# MaxMotor.net
KiCad netlist of a schematic drawn in EAGLE
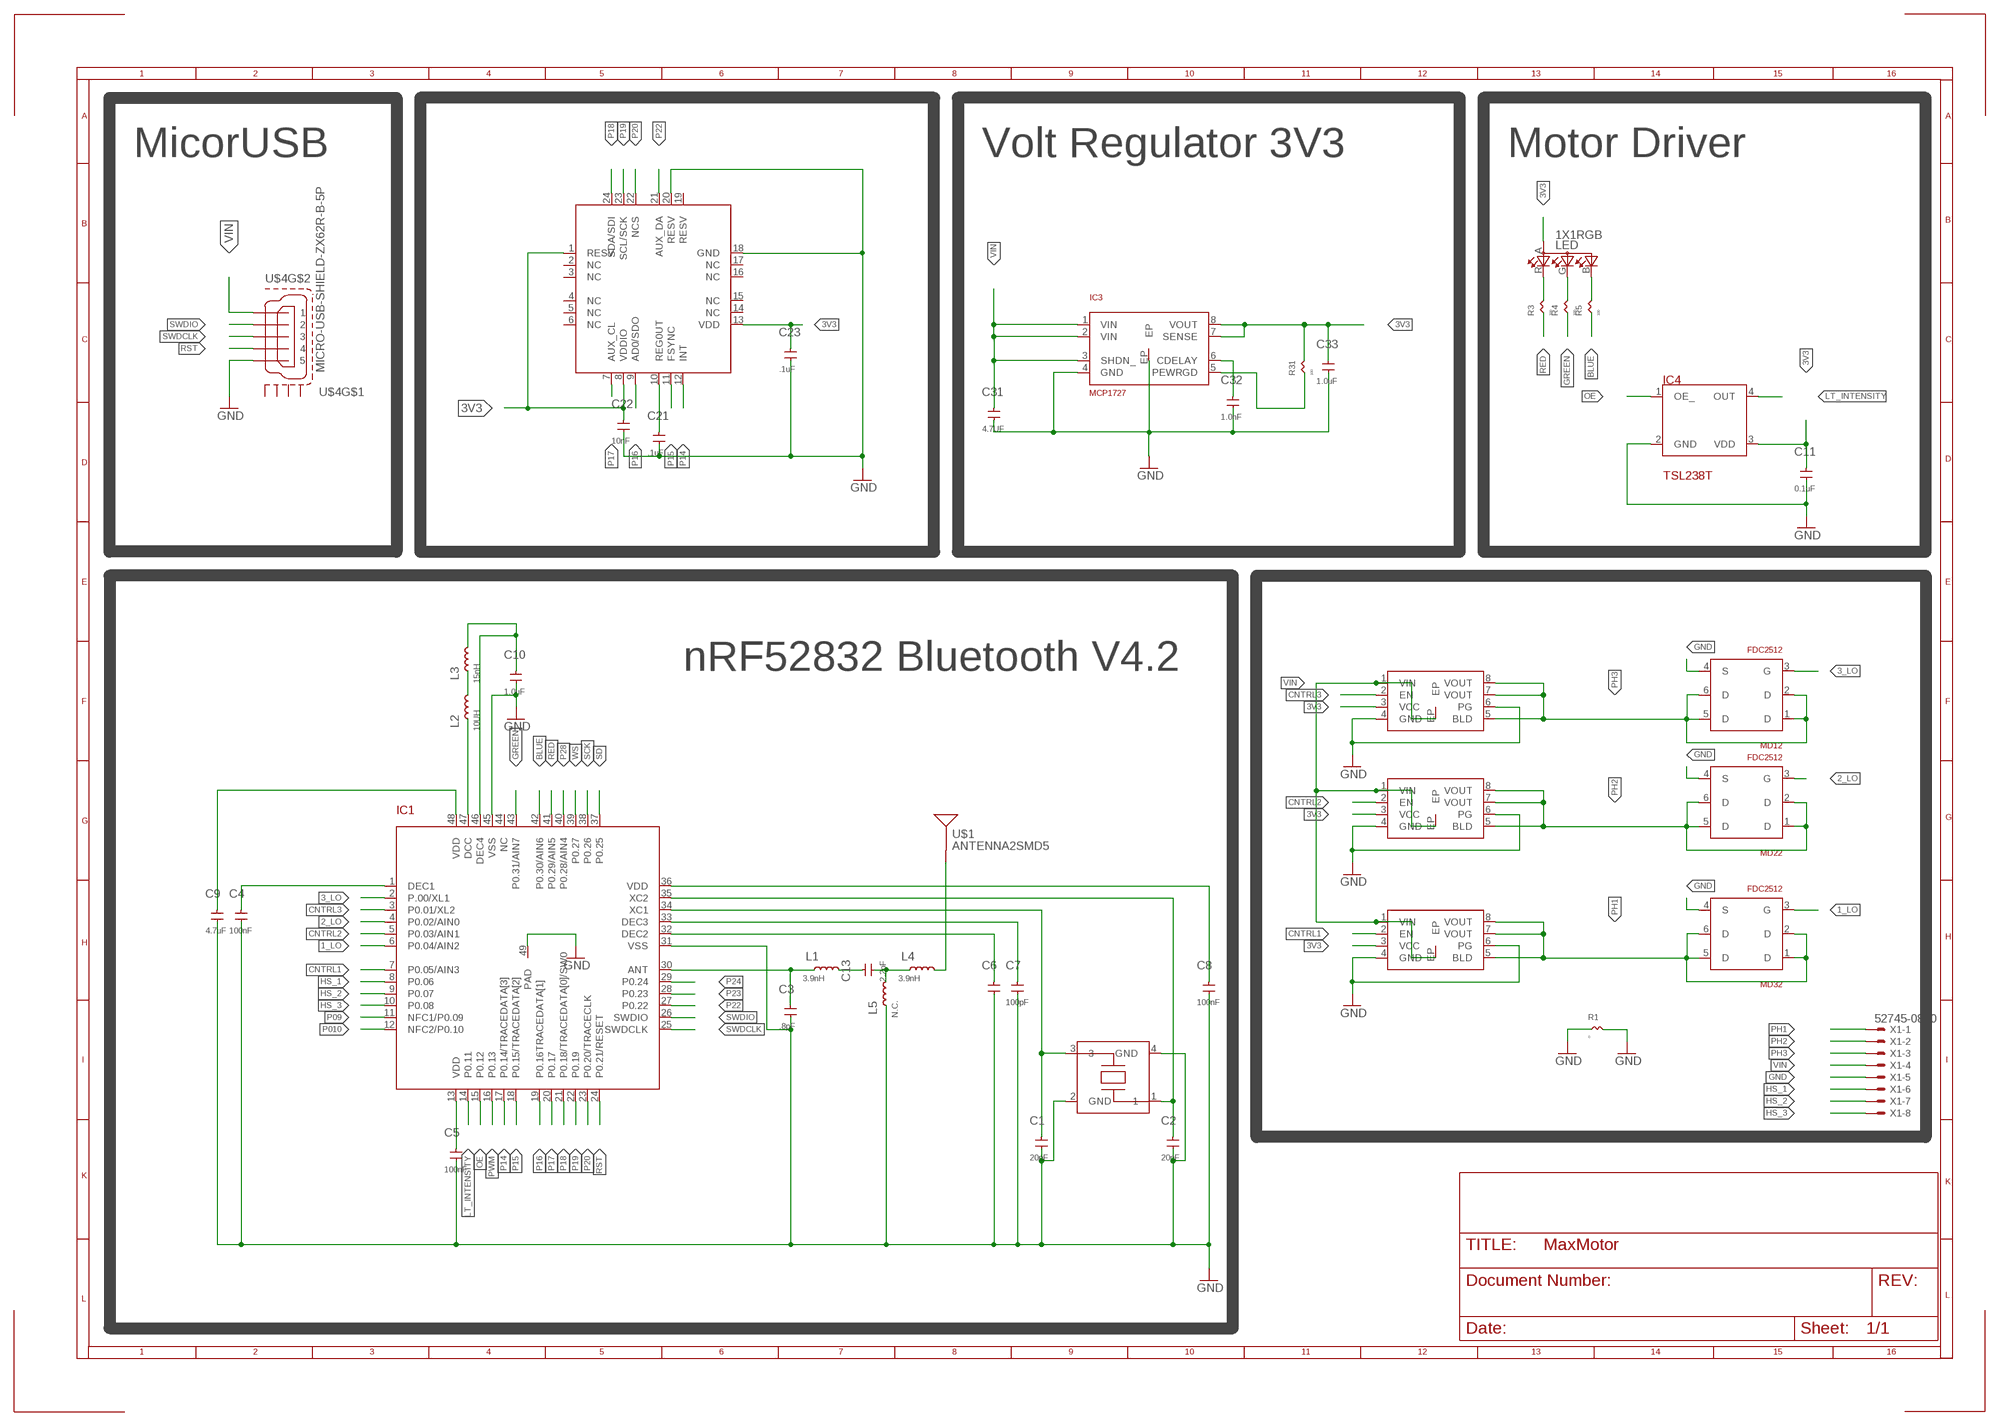
[diagram p0: schematic, sheet 1, part 1 of 2]
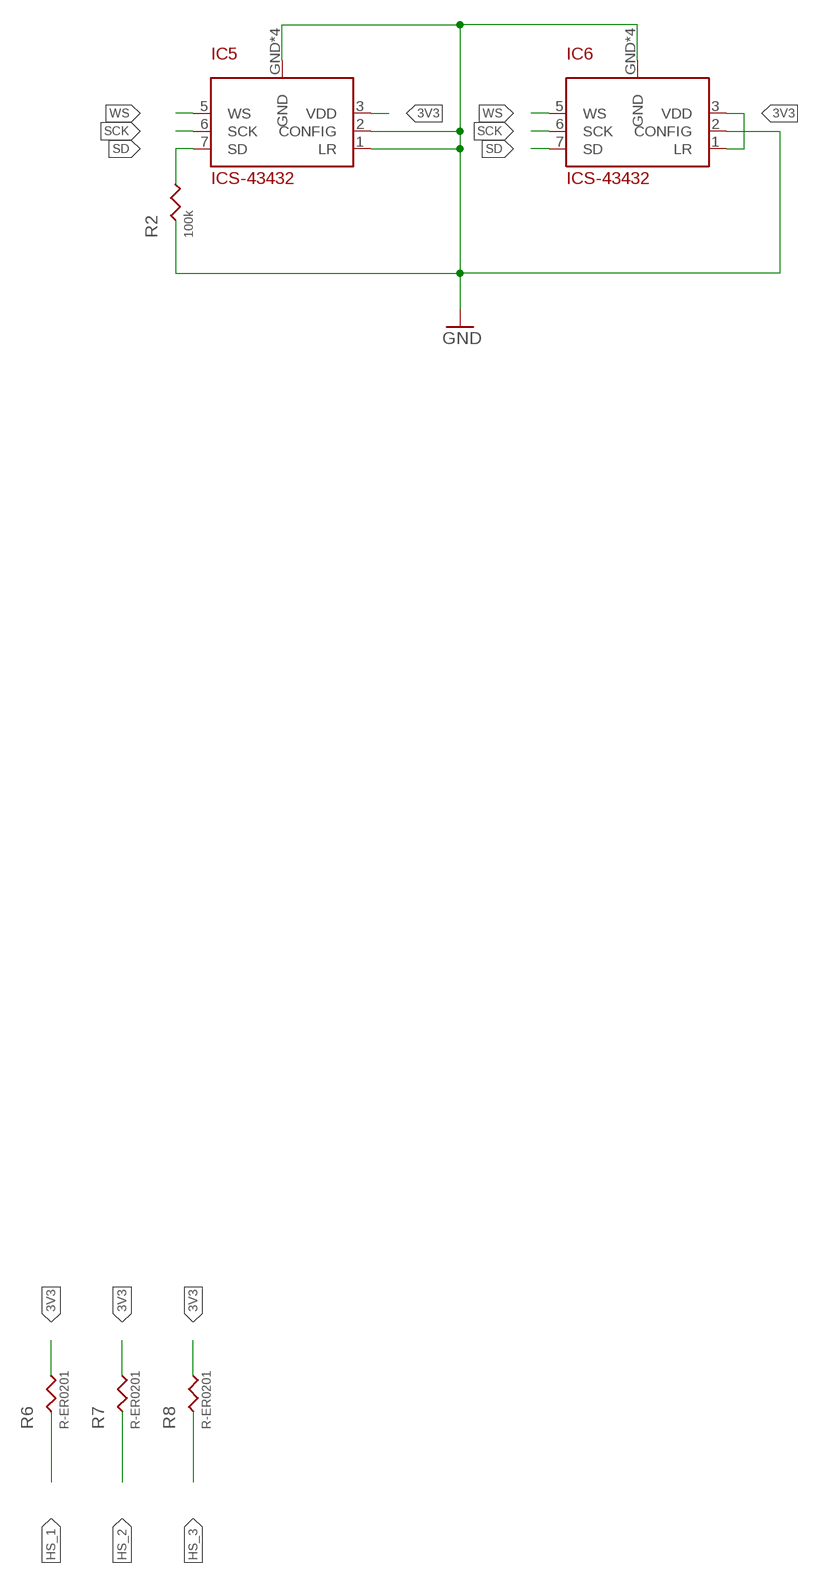
[diagram p1: schematic, sheet 1, part 2 of 2]

(export (version "E")
  (design (tool "Eeschema 10.0.6"))
  (components
    (comp (ref "C1")
      (value "20pF")
      (footprint "eagle-import:C0402")
      (libsource (lib "eagle-import") (part "C-ERC0402"))
    )
    (comp (ref "C2")
      (value "20pF")
      (footprint "eagle-import:C0402")
      (libsource (lib "eagle-import") (part "C-ERC0402"))
    )
    (comp (ref "C3")
      (value ".8pF")
      (footprint "eagle-import:C0402")
      (libsource (lib "eagle-import") (part "C-ERC0402"))
    )
    (comp (ref "C4")
      (value "100nF")
      (footprint "eagle-import:C0402")
      (libsource (lib "eagle-import") (part "C-ERC0402"))
    )
    (comp (ref "C5")
      (value "100nF")
      (footprint "eagle-import:C0402")
      (libsource (lib "eagle-import") (part "C-ERC0402"))
    )
    (comp (ref "C6")
      (value "C-ERC0402")
      (footprint "eagle-import:C0402")
      (libsource (lib "eagle-import") (part "C-ERC0402"))
    )
    (comp (ref "C7")
      (value "100pF")
      (footprint "eagle-import:C0402")
      (libsource (lib "eagle-import") (part "C-ERC0402"))
    )
    (comp (ref "C8")
      (value "100nF")
      (footprint "eagle-import:C0402")
      (libsource (lib "eagle-import") (part "C-ERC0402"))
    )
    (comp (ref "C9")
      (value "4.7uF")
      (footprint "eagle-import:C0805")
      (libsource (lib "eagle-import") (part "C-ER"))
    )
    (comp (ref "C10")
      (value "1.0uF")
      (footprint "eagle-import:C0402")
      (libsource (lib "eagle-import") (part "C-ERC0402"))
    )
    (comp (ref "C11")
      (value "0.1uF")
      (footprint "eagle-import:C0402")
      (libsource (lib "eagle-import") (part "C-ERC0402"))
    )
    (comp (ref "C13")
      (value "2.2pF")
      (footprint "eagle-import:C0402")
      (libsource (lib "eagle-import") (part "C-ERC0402"))
    )
    (comp (ref "C21")
      (value ".1uF")
      (footprint "eagle-import:C0402")
      (libsource (lib "eagle-import") (part "C-ERC0402"))
    )
    (comp (ref "C22")
      (value "10nF")
      (footprint "eagle-import:C0402")
      (libsource (lib "eagle-import") (part "C-ERC0402"))
    )
    (comp (ref "C23")
      (value ".1uF")
      (footprint "eagle-import:C0402")
      (libsource (lib "eagle-import") (part "C-ERC0402"))
    )
    (comp (ref "C31")
      (value "4.7UF")
      (footprint "eagle-import:C0805")
      (libsource (lib "eagle-import") (part "C-ER"))
    )
    (comp (ref "C32")
      (value "1.0nF")
      (footprint "eagle-import:C0402")
      (libsource (lib "eagle-import") (part "C-ERC0402"))
    )
    (comp (ref "C33")
      (value "1.0uF")
      (footprint "eagle-import:C0402")
      (libsource (lib "eagle-import") (part "C-ERC0402"))
    )
    (comp (ref "IC1")
      (value "NRF52832")
      (footprint "eagle-import:QFN48")
      (libsource (lib "eagle-import") (part "NRF52832"))
    )
    (comp (ref "IC2")
      (value "MPU9250_CORRECTED")
      (footprint "eagle-import:3X3_24_QFN_CORRECTED")
      (libsource (lib "eagle-import") (part "MPU9250_CORRECTED"))
    )
    (comp (ref "IC3")
      (value "MCP1727")
      (footprint "eagle-import:DFN8-3X3")
      (libsource (lib "eagle-import") (part "MCP1727"))
    )
    (comp (ref "IC4")
      (value "TSL238T")
      (footprint "eagle-import:T4")
      (libsource (lib "eagle-import") (part "TSL238T"))
    )
    (comp (ref "IC5")
      (value "ICS-43432")
      (footprint "eagle-import:ICS-43432")
      (libsource (lib "eagle-import") (part "ICS-43432"))
    )
    (comp (ref "IC6")
      (value "ICS-43432")
      (footprint "eagle-import:ICS-43432")
      (libsource (lib "eagle-import") (part "ICS-43432"))
    )
    (comp (ref "L1")
      (value "3.9nH")
      (footprint "eagle-import:R0402")
      (libsource (lib "eagle-import") (part "L-ERL402"))
    )
    (comp (ref "L2")
      (value "10UH")
      (footprint "eagle-import:R0603")
      (libsource (lib "eagle-import") (part "L-ERL603"))
    )
    (comp (ref "L3")
      (value "15nH")
      (footprint "eagle-import:R0402")
      (libsource (lib "eagle-import") (part "L-ERL402"))
    )
    (comp (ref "L4")
      (value "3.9nH")
      (footprint "eagle-import:R0402")
      (libsource (lib "eagle-import") (part "L-ERL402"))
    )
    (comp (ref "L5")
      (value "N.C.")
      (footprint "eagle-import:R0402")
      (libsource (lib "eagle-import") (part "L-ERL402"))
    )
    (comp (ref "LED")
      (value "1X1RGB")
      (footprint "eagle-import:1X1")
      (libsource (lib "eagle-import") (part "1X1RGB"))
    )
    (comp (ref "MD12")
      (value "FDC2512")
      (footprint "eagle-import:SSOT6")
      (libsource (lib "eagle-import") (part "FDC2512"))
    )
    (comp (ref "MD22")
      (value "FDC2512")
      (footprint "eagle-import:SSOT6")
      (libsource (lib "eagle-import") (part "FDC2512"))
    )
    (comp (ref "MD32")
      (value "FDC2512")
      (footprint "eagle-import:SSOT6")
      (libsource (lib "eagle-import") (part "FDC2512"))
    )
    (comp (ref "R1")
      (value "0")
      (footprint "eagle-import:R0402")
      (libsource (lib "eagle-import") (part "R-ER-TINYR402"))
    )
    (comp (ref "R2")
      (value "100k")
      (footprint "eagle-import:R0402")
      (libsource (lib "eagle-import") (part "R-ERR0402"))
    )
    (comp (ref "R3")
      (value "100")
      (footprint "eagle-import:R0402")
      (libsource (lib "eagle-import") (part "R-ER-TINYR402"))
    )
    (comp (ref "R4")
      (value "100")
      (footprint "eagle-import:R0402")
      (libsource (lib "eagle-import") (part "R-ER-TINYR402"))
    )
    (comp (ref "R5")
      (value "100")
      (footprint "eagle-import:R0402")
      (libsource (lib "eagle-import") (part "R-ER-TINYR402"))
    )
    (comp (ref "R6")
      (value "R-ER0201")
      (footprint "eagle-import:R0201")
      (libsource (lib "eagle-import") (part "R-ER0201"))
    )
    (comp (ref "R7")
      (value "R-ER0201")
      (footprint "eagle-import:R0201")
      (libsource (lib "eagle-import") (part "R-ER0201"))
    )
    (comp (ref "R8")
      (value "R-ER0201")
      (footprint "eagle-import:R0201")
      (libsource (lib "eagle-import") (part "R-ER0201"))
    )
    (comp (ref "R31")
      (value "100")
      (footprint "eagle-import:R0402")
      (libsource (lib "eagle-import") (part "R-ER-TINYR402"))
    )
    (comp (ref "U$1")
      (value "ANTENNA2SMD5")
      (footprint "eagle-import:ANTENNA-CHIP5")
      (libsource (lib "eagle-import") (part "ANTENNA2SMD5"))
    )
    (comp (ref "U$2")
      (value "NCP45524/25")
      (footprint "eagle-import:DFN8")
      (libsource (lib "eagle-import") (part "NCP45524/25"))
    )
    (comp (ref "U$4")
      (value "MICRO-USB-SHIELD-ZX62R-B-5P")
      (footprint "eagle-import:ZX62R-B-5P")
      (libsource (lib "eagle-import") (part "MICRO-USB-SHIELD-ZX62R-B-5P"))
    )
    (comp (ref "U$5")
      (value "NCP45524/25")
      (footprint "eagle-import:DFN8")
      (libsource (lib "eagle-import") (part "NCP45524/25"))
    )
    (comp (ref "U$6")
      (value "NCP45524/25")
      (footprint "eagle-import:DFN8")
      (libsource (lib "eagle-import") (part "NCP45524/25"))
    )
    (comp (ref "X1")
      (value "52745-0890")
      (footprint "eagle-import:52745-0890")
      (libsource (lib "eagle-import") (part "52745-0890"))
    )
    (comp (ref "XTL16M")
      (value "FA-128")
      (footprint "eagle-import:FA-128")
      (libsource (lib "eagle-import") (part "FA-128"))
    )
  )
  (nets
    (net (code "1") (name "1_LO") (class "Default")
      (node (ref "IC1") (pin "6") (pinfunction "P0.04/AIN2_6") (pintype "bidirectional"))
      (node (ref "MD32") (pin "3") (pinfunction "G_3") (pintype "bidirectional"))
    )
    (net (code "2") (name "2_LO") (class "Default")
      (node (ref "IC1") (pin "4") (pinfunction "P0.02/AIN0_4") (pintype "bidirectional"))
      (node (ref "MD22") (pin "3") (pinfunction "G_3") (pintype "bidirectional"))
    )
    (net (code "3") (name "3V3") (class "Default")
      (node (ref "C11") (pin "2") (pinfunction "P$2_2") (pintype "bidirectional"))
      (node (ref "C22") (pin "2") (pinfunction "P$2_2") (pintype "bidirectional"))
      (node (ref "C23") (pin "2") (pinfunction "P$2_2") (pintype "bidirectional"))
      (node (ref "C33") (pin "2") (pinfunction "P$2_2") (pintype "bidirectional"))
      (node (ref "C5") (pin "2") (pinfunction "P$2_2") (pintype "bidirectional"))
      (node (ref "C8") (pin "2") (pinfunction "P$2_2") (pintype "bidirectional"))
      (node (ref "C9") (pin "2") (pinfunction "P$2_2") (pintype "bidirectional"))
      (node (ref "IC1") (pin "13") (pinfunction "VDD_13") (pintype "bidirectional"))
      (node (ref "IC1") (pin "36") (pinfunction "VDD_36") (pintype "bidirectional"))
      (node (ref "IC1") (pin "48") (pinfunction "VDD_48") (pintype "bidirectional"))
      (node (ref "IC2") (pin "1") (pinfunction "RESV_1") (pintype "bidirectional"))
      (node (ref "IC2") (pin "13") (pinfunction "VDD_13") (pintype "bidirectional"))
      (node (ref "IC2") (pin "8") (pinfunction "VDDIO_8") (pintype "bidirectional"))
      (node (ref "IC3") (pin "7") (pinfunction "SENSE_7") (pintype "bidirectional"))
      (node (ref "IC3") (pin "8") (pinfunction "VOUT_8") (pintype "bidirectional"))
      (node (ref "IC4") (pin "3") (pinfunction "VDD_3") (pintype "bidirectional"))
      (node (ref "IC5") (pin "3") (pinfunction "VDD_3") (pintype "bidirectional"))
      (node (ref "IC6") (pin "1") (pinfunction "LR_1") (pintype "bidirectional"))
      (node (ref "IC6") (pin "3") (pinfunction "VDD_3") (pintype "bidirectional"))
      (node (ref "LED") (pin "A") (pinfunction "A2_A") (pintype "passive"))
      (node (ref "R31") (pin "2") (pinfunction "P$2_2") (pintype "bidirectional"))
      (node (ref "R6") (pin "2") (pinfunction "P$2_2") (pintype "bidirectional"))
      (node (ref "R7") (pin "2") (pinfunction "P$2_2") (pintype "bidirectional"))
      (node (ref "R8") (pin "2") (pinfunction "P$2_2") (pintype "bidirectional"))
      (node (ref "U$2") (pin "3") (pinfunction "VCC_3") (pintype "bidirectional"))
      (node (ref "U$5") (pin "3") (pinfunction "VCC_3") (pintype "bidirectional"))
      (node (ref "U$6") (pin "3") (pinfunction "VCC_3") (pintype "bidirectional"))
    )
    (net (code "4") (name "3_LO") (class "Default")
      (node (ref "IC1") (pin "2") (pinfunction "P.00/XL1_2") (pintype "bidirectional"))
      (node (ref "MD12") (pin "3") (pinfunction "G_3") (pintype "bidirectional"))
    )
    (net (code "5") (name "BLUE") (class "Default")
      (node (ref "IC1") (pin "42") (pinfunction "P0.30/AIN6_42") (pintype "bidirectional"))
      (node (ref "R5") (pin "1") (pinfunction "P$1_1") (pintype "bidirectional"))
    )
    (net (code "6") (name "CNTRL1") (class "Default")
      (node (ref "IC1") (pin "7") (pinfunction "P0.05/AIN3_7") (pintype "bidirectional"))
      (node (ref "U$6") (pin "2") (pinfunction "EN_2") (pintype "bidirectional"))
    )
    (net (code "7") (name "CNTRL2") (class "Default")
      (node (ref "IC1") (pin "5") (pinfunction "P0.03/AIN1_5") (pintype "bidirectional"))
      (node (ref "U$5") (pin "2") (pinfunction "EN_2") (pintype "bidirectional"))
    )
    (net (code "8") (name "CNTRL3") (class "Default")
      (node (ref "IC1") (pin "3") (pinfunction "P0.01/XL2_3") (pintype "bidirectional"))
      (node (ref "U$2") (pin "2") (pinfunction "EN_2") (pintype "bidirectional"))
    )
    (net (code "9") (name "GND") (class "Default")
      (node (ref "C1") (pin "1") (pinfunction "P$1_1") (pintype "bidirectional"))
      (node (ref "C10") (pin "1") (pinfunction "P$1_1") (pintype "bidirectional"))
      (node (ref "C11") (pin "1") (pinfunction "P$1_1") (pintype "bidirectional"))
      (node (ref "C2") (pin "1") (pinfunction "P$1_1") (pintype "bidirectional"))
      (node (ref "C21") (pin "1") (pinfunction "P$1_1") (pintype "bidirectional"))
      (node (ref "C22") (pin "1") (pinfunction "P$1_1") (pintype "bidirectional"))
      (node (ref "C23") (pin "1") (pinfunction "P$1_1") (pintype "bidirectional"))
      (node (ref "C3") (pin "1") (pinfunction "P$1_1") (pintype "bidirectional"))
      (node (ref "C31") (pin "1") (pinfunction "P$1_1") (pintype "bidirectional"))
      (node (ref "C32") (pin "1") (pinfunction "P$1_1") (pintype "bidirectional"))
      (node (ref "C33") (pin "1") (pinfunction "P$1_1") (pintype "bidirectional"))
      (node (ref "C4") (pin "1") (pinfunction "P$1_1") (pintype "bidirectional"))
      (node (ref "C5") (pin "1") (pinfunction "P$1_1") (pintype "bidirectional"))
      (node (ref "C6") (pin "1") (pinfunction "P$1_1") (pintype "bidirectional"))
      (node (ref "C7") (pin "1") (pinfunction "P$1_1") (pintype "bidirectional"))
      (node (ref "C8") (pin "1") (pinfunction "P$1_1") (pintype "bidirectional"))
      (node (ref "C9") (pin "1") (pinfunction "P$1_1") (pintype "bidirectional"))
      (node (ref "IC1") (pin "31") (pinfunction "VSS_31") (pintype "bidirectional"))
      (node (ref "IC1") (pin "45") (pinfunction "VSS_45") (pintype "bidirectional"))
      (node (ref "IC1") (pin "49") (pinfunction "PAD_49") (pintype "bidirectional"))
      (node (ref "IC2") (pin "18") (pinfunction "GND_18") (pintype "bidirectional"))
      (node (ref "IC2") (pin "20") (pinfunction "RESV_20") (pintype "bidirectional"))
      (node (ref "IC3") (pin "4") (pinfunction "GND_4") (pintype "bidirectional"))
      (node (ref "IC3") (pin "EP") (pinfunction "EP_EP") (pintype "bidirectional"))
      (node (ref "IC4") (pin "2") (pinfunction "GND_2") (pintype "bidirectional"))
      (node (ref "IC5") (pin "1") (pinfunction "LR_1") (pintype "bidirectional"))
      (node (ref "IC5") (pin "2") (pinfunction "CONFIG_2") (pintype "bidirectional"))
      (node (ref "IC5") (pin "GND") (pinfunction "GND_GND") (pintype "bidirectional"))
      (node (ref "IC5") (pin "GND@") (pinfunction "GND_GND@") (pintype "bidirectional"))
      (node (ref "IC5") (pin "GND@1") (pinfunction "GND_GND@1") (pintype "bidirectional"))
      (node (ref "IC5") (pin "GND@2") (pinfunction "GND_GND@2") (pintype "bidirectional"))
      (node (ref "IC6") (pin "2") (pinfunction "CONFIG_2") (pintype "bidirectional"))
      (node (ref "IC6") (pin "GND") (pinfunction "GND_GND") (pintype "bidirectional"))
      (node (ref "IC6") (pin "GND@") (pinfunction "GND_GND@") (pintype "bidirectional"))
      (node (ref "IC6") (pin "GND@1") (pinfunction "GND_GND@1") (pintype "bidirectional"))
      (node (ref "IC6") (pin "GND@2") (pinfunction "GND_GND@2") (pintype "bidirectional"))
      (node (ref "L5") (pin "1") (pinfunction "P$1_1") (pintype "bidirectional"))
      (node (ref "MD12") (pin "4") (pinfunction "S_4") (pintype "bidirectional"))
      (node (ref "MD22") (pin "4") (pinfunction "S_4") (pintype "bidirectional"))
      (node (ref "MD32") (pin "4") (pinfunction "S_4") (pintype "bidirectional"))
      (node (ref "R1") (pin "1") (pinfunction "P$1_1") (pintype "bidirectional"))
      (node (ref "R1") (pin "2") (pinfunction "P$2_2") (pintype "bidirectional"))
      (node (ref "R2") (pin "1") (pinfunction "P$1_1") (pintype "bidirectional"))
      (node (ref "U$2") (pin "4") (pinfunction "GND_4") (pintype "bidirectional"))
      (node (ref "U$2") (pin "6") (pinfunction "PG_6") (pintype "bidirectional"))
      (node (ref "U$4") (pin "1") (pinfunction "5_1") (pintype "input"))
      (node (ref "U$5") (pin "4") (pinfunction "GND_4") (pintype "bidirectional"))
      (node (ref "U$5") (pin "6") (pinfunction "PG_6") (pintype "bidirectional"))
      (node (ref "U$6") (pin "4") (pinfunction "GND_4") (pintype "bidirectional"))
      (node (ref "U$6") (pin "6") (pinfunction "PG_6") (pintype "bidirectional"))
      (node (ref "X1") (pin "5") (pinfunction "S_5") (pintype "passive"))
      (node (ref "XTL16M") (pin "2") (pinfunction "GND_2") (pintype "bidirectional"))
      (node (ref "XTL16M") (pin "4") (pinfunction "GND_4") (pintype "bidirectional"))
    )
    (net (code "10") (name "GREEN") (class "Default")
      (node (ref "IC1") (pin "43") (pinfunction "P0.31/AIN7_43") (pintype "bidirectional"))
      (node (ref "R4") (pin "1") (pinfunction "P$1_1") (pintype "bidirectional"))
    )
    (net (code "11") (name "HS_1") (class "Default")
      (node (ref "IC1") (pin "8") (pinfunction "P0.06_8") (pintype "bidirectional"))
      (node (ref "R6") (pin "1") (pinfunction "P$1_1") (pintype "bidirectional"))
      (node (ref "X1") (pin "6") (pinfunction "S_6") (pintype "passive"))
    )
    (net (code "12") (name "HS_2") (class "Default")
      (node (ref "IC1") (pin "9") (pinfunction "P0.07_9") (pintype "bidirectional"))
      (node (ref "R7") (pin "1") (pinfunction "P$1_1") (pintype "bidirectional"))
      (node (ref "X1") (pin "7") (pinfunction "S_7") (pintype "passive"))
    )
    (net (code "13") (name "HS_3") (class "Default")
      (node (ref "IC1") (pin "10") (pinfunction "P0.08_10") (pintype "bidirectional"))
      (node (ref "R8") (pin "1") (pinfunction "P$1_1") (pintype "bidirectional"))
      (node (ref "X1") (pin "8") (pinfunction "S_8") (pintype "passive"))
    )
    (net (code "14") (name "LT_INTENSITY") (class "Default")
      (node (ref "IC1") (pin "14") (pinfunction "P0.11_14") (pintype "bidirectional"))
      (node (ref "IC4") (pin "4") (pinfunction "OUT_4") (pintype "bidirectional"))
    )
    (net (code "15") (name "Net-(C1-P$2)") (class "Default")
      (node (ref "C1") (pin "2") (pinfunction "P$2_2") (pintype "bidirectional"))
      (node (ref "IC1") (pin "34") (pinfunction "XC1_34") (pintype "bidirectional"))
      (node (ref "XTL16M") (pin "3") (pinfunction "3_3") (pintype "bidirectional"))
    )
    (net (code "16") (name "Net-(C2-P$2)") (class "Default")
      (node (ref "C2") (pin "2") (pinfunction "P$2_2") (pintype "bidirectional"))
      (node (ref "IC1") (pin "35") (pinfunction "XC2_35") (pintype "bidirectional"))
      (node (ref "XTL16M") (pin "1") (pinfunction "1_1") (pintype "bidirectional"))
    )
    (net (code "17") (name "Net-(C3-P$2)") (class "Default")
      (node (ref "C3") (pin "2") (pinfunction "P$2_2") (pintype "bidirectional"))
      (node (ref "IC1") (pin "30") (pinfunction "ANT_30") (pintype "bidirectional"))
      (node (ref "L1") (pin "1") (pinfunction "P$1_1") (pintype "bidirectional"))
    )
    (net (code "18") (name "Net-(C4-P$2)") (class "Default")
      (node (ref "C4") (pin "2") (pinfunction "P$2_2") (pintype "bidirectional"))
      (node (ref "IC1") (pin "1") (pinfunction "DEC1_1") (pintype "bidirectional"))
    )
    (net (code "19") (name "Net-(C6-P$2)") (class "Default")
      (node (ref "C6") (pin "2") (pinfunction "P$2_2") (pintype "bidirectional"))
      (node (ref "IC1") (pin "32") (pinfunction "DEC2_32") (pintype "bidirectional"))
    )
    (net (code "20") (name "Net-(C7-P$2)") (class "Default")
      (node (ref "C7") (pin "2") (pinfunction "P$2_2") (pintype "bidirectional"))
      (node (ref "IC1") (pin "33") (pinfunction "DEC3_33") (pintype "bidirectional"))
    )
    (net (code "21") (name "Net-(C10-P$2)") (class "Default")
      (node (ref "C10") (pin "2") (pinfunction "P$2_2") (pintype "bidirectional"))
      (node (ref "IC1") (pin "46") (pinfunction "DEC4_46") (pintype "bidirectional"))
      (node (ref "L3") (pin "2") (pinfunction "P$2_2") (pintype "bidirectional"))
    )
    (net (code "22") (name "Net-(C13-P$1)") (class "Default")
      (node (ref "C13") (pin "1") (pinfunction "P$1_1") (pintype "bidirectional"))
      (node (ref "L4") (pin "1") (pinfunction "P$1_1") (pintype "bidirectional"))
      (node (ref "L5") (pin "2") (pinfunction "P$2_2") (pintype "bidirectional"))
    )
    (net (code "23") (name "Net-(C13-P$2)") (class "Default")
      (node (ref "C13") (pin "2") (pinfunction "P$2_2") (pintype "bidirectional"))
      (node (ref "L1") (pin "2") (pinfunction "P$2_2") (pintype "bidirectional"))
    )
    (net (code "24") (name "Net-(C21-P$2)") (class "Default")
      (node (ref "C21") (pin "2") (pinfunction "P$2_2") (pintype "bidirectional"))
      (node (ref "IC2") (pin "10") (pinfunction "REG0UT_10") (pintype "bidirectional"))
    )
    (net (code "25") (name "Net-(C32-P$2)") (class "Default")
      (node (ref "C32") (pin "2") (pinfunction "P$2_2") (pintype "bidirectional"))
      (node (ref "IC3") (pin "6") (pinfunction "CDELAY_6") (pintype "bidirectional"))
    )
    (net (code "26") (name "Net-(IC1-DCC)") (class "Default")
      (node (ref "IC1") (pin "47") (pinfunction "DCC_47") (pintype "bidirectional"))
      (node (ref "L2") (pin "1") (pinfunction "P$1_1") (pintype "bidirectional"))
    )
    (net (code "27") (name "Net-(IC3-PEWRGD)") (class "Default")
      (node (ref "IC3") (pin "5") (pinfunction "PEWRGD_5") (pintype "bidirectional"))
      (node (ref "R31") (pin "1") (pinfunction "P$1_1") (pintype "bidirectional"))
    )
    (net (code "28") (name "Net-(L2-P$2)") (class "Default")
      (node (ref "L2") (pin "2") (pinfunction "P$2_2") (pintype "bidirectional"))
      (node (ref "L3") (pin "1") (pinfunction "P$1_1") (pintype "bidirectional"))
    )
    (net (code "29") (name "Net-(L4-P$2)") (class "Default")
      (node (ref "L4") (pin "2") (pinfunction "P$2_2") (pintype "bidirectional"))
      (node (ref "U$1") (pin "FEED") (pinfunction "SIGNAL_FEED") (pintype "bidirectional"))
    )
    (net (code "30") (name "Net-(LED-CBLUE)") (class "Default")
      (node (ref "LED") (pin "G") (pinfunction "CBLUE_G") (pintype "passive"))
      (node (ref "R4") (pin "2") (pinfunction "P$2_2") (pintype "bidirectional"))
    )
    (net (code "31") (name "Net-(LED-CGREEN)") (class "Default")
      (node (ref "LED") (pin "B") (pinfunction "CGREEN_B") (pintype "passive"))
      (node (ref "R5") (pin "2") (pinfunction "P$2_2") (pintype "bidirectional"))
    )
    (net (code "32") (name "Net-(LED-CRED)") (class "Default")
      (node (ref "LED") (pin "R") (pinfunction "CRED_R") (pintype "passive"))
      (node (ref "R3") (pin "2") (pinfunction "P$2_2") (pintype "bidirectional"))
    )
    (net (code "33") (name "OE") (class "Default")
      (node (ref "IC1") (pin "15") (pinfunction "P0.12_15") (pintype "bidirectional"))
      (node (ref "IC4") (pin "1") (pinfunction "OE__1") (pintype "bidirectional"))
    )
    (net (code "34") (name "P09") (class "Default")
      (node (ref "IC1") (pin "11") (pinfunction "NFC1/P0.09_11") (pintype "bidirectional"))
    )
    (net (code "35") (name "P010") (class "Default")
      (node (ref "IC1") (pin "12") (pinfunction "NFC2/P0.10_12") (pintype "bidirectional"))
    )
    (net (code "36") (name "P14") (class "Default")
      (node (ref "IC1") (pin "17") (pinfunction "P0.14/TRACEDATA[3]_17") (pintype "bidirectional"))
      (node (ref "IC2") (pin "12") (pinfunction "INT_12") (pintype "bidirectional"))
    )
    (net (code "37") (name "P15") (class "Default")
      (node (ref "IC1") (pin "18") (pinfunction "P0.15/TRACEDATA[2]_18") (pintype "bidirectional"))
      (node (ref "IC2") (pin "11") (pinfunction "FSYNC_11") (pintype "bidirectional"))
    )
    (net (code "38") (name "P16") (class "Default")
      (node (ref "IC1") (pin "19") (pinfunction "P0.16TRACEDATA[1]_19") (pintype "bidirectional"))
      (node (ref "IC2") (pin "9") (pinfunction "AD0/SDO_9") (pintype "bidirectional"))
    )
    (net (code "39") (name "P17") (class "Default")
      (node (ref "IC1") (pin "20") (pinfunction "P0.17_20") (pintype "bidirectional"))
      (node (ref "IC2") (pin "7") (pinfunction "AUX_CL_7") (pintype "bidirectional"))
    )
    (net (code "40") (name "P18") (class "Default")
      (node (ref "IC1") (pin "21") (pinfunction "P0.18/TRACEDATA[0]/SW0_21") (pintype "bidirectional"))
      (node (ref "IC2") (pin "24") (pinfunction "SDA/SDI_24") (pintype "bidirectional"))
    )
    (net (code "41") (name "P19") (class "Default")
      (node (ref "IC1") (pin "22") (pinfunction "P0.19_22") (pintype "bidirectional"))
      (node (ref "IC2") (pin "23") (pinfunction "SCL/SCK_23") (pintype "bidirectional"))
    )
    (net (code "42") (name "P20") (class "Default")
      (node (ref "IC1") (pin "23") (pinfunction "P0.20/TRACECLK_23") (pintype "bidirectional"))
      (node (ref "IC2") (pin "22") (pinfunction "NCS_22") (pintype "bidirectional"))
    )
    (net (code "43") (name "P22") (class "Default")
      (node (ref "IC1") (pin "27") (pinfunction "P0.22_27") (pintype "bidirectional"))
      (node (ref "IC2") (pin "21") (pinfunction "AUX_DA_21") (pintype "bidirectional"))
    )
    (net (code "44") (name "P23") (class "Default")
      (node (ref "IC1") (pin "28") (pinfunction "P0.23_28") (pintype "bidirectional"))
    )
    (net (code "45") (name "P24") (class "Default")
      (node (ref "IC1") (pin "29") (pinfunction "P0.24_29") (pintype "bidirectional"))
    )
    (net (code "46") (name "P28") (class "Default")
      (node (ref "IC1") (pin "40") (pinfunction "P0.28/AIN4_40") (pintype "bidirectional"))
    )
    (net (code "47") (name "PH1") (class "Default")
      (node (ref "MD32") (pin "1") (pinfunction "D_1") (pintype "bidirectional"))
      (node (ref "MD32") (pin "2") (pinfunction "D_2") (pintype "bidirectional"))
      (node (ref "MD32") (pin "5") (pinfunction "D_5") (pintype "bidirectional"))
      (node (ref "MD32") (pin "6") (pinfunction "D_6") (pintype "bidirectional"))
      (node (ref "U$6") (pin "5") (pinfunction "BLD_5") (pintype "bidirectional"))
      (node (ref "U$6") (pin "7") (pinfunction "VOUT_7") (pintype "bidirectional"))
      (node (ref "U$6") (pin "8") (pinfunction "VOUT_8") (pintype "bidirectional"))
      (node (ref "X1") (pin "1") (pinfunction "S_1") (pintype "passive"))
    )
    (net (code "48") (name "PH2") (class "Default")
      (node (ref "MD22") (pin "1") (pinfunction "D_1") (pintype "bidirectional"))
      (node (ref "MD22") (pin "2") (pinfunction "D_2") (pintype "bidirectional"))
      (node (ref "MD22") (pin "5") (pinfunction "D_5") (pintype "bidirectional"))
      (node (ref "MD22") (pin "6") (pinfunction "D_6") (pintype "bidirectional"))
      (node (ref "U$5") (pin "5") (pinfunction "BLD_5") (pintype "bidirectional"))
      (node (ref "U$5") (pin "7") (pinfunction "VOUT_7") (pintype "bidirectional"))
      (node (ref "U$5") (pin "8") (pinfunction "VOUT_8") (pintype "bidirectional"))
      (node (ref "X1") (pin "2") (pinfunction "S_2") (pintype "passive"))
    )
    (net (code "49") (name "PH3") (class "Default")
      (node (ref "MD12") (pin "1") (pinfunction "D_1") (pintype "bidirectional"))
      (node (ref "MD12") (pin "2") (pinfunction "D_2") (pintype "bidirectional"))
      (node (ref "MD12") (pin "5") (pinfunction "D_5") (pintype "bidirectional"))
      (node (ref "MD12") (pin "6") (pinfunction "D_6") (pintype "bidirectional"))
      (node (ref "U$2") (pin "5") (pinfunction "BLD_5") (pintype "bidirectional"))
      (node (ref "U$2") (pin "7") (pinfunction "VOUT_7") (pintype "bidirectional"))
      (node (ref "U$2") (pin "8") (pinfunction "VOUT_8") (pintype "bidirectional"))
      (node (ref "X1") (pin "3") (pinfunction "S_3") (pintype "passive"))
    )
    (net (code "50") (name "PWM") (class "Default")
      (node (ref "IC1") (pin "16") (pinfunction "P0.13_16") (pintype "bidirectional"))
    )
    (net (code "51") (name "RED") (class "Default")
      (node (ref "IC1") (pin "41") (pinfunction "P0.29/AIN5_41") (pintype "bidirectional"))
      (node (ref "R3") (pin "1") (pinfunction "P$1_1") (pintype "bidirectional"))
    )
    (net (code "52") (name "RST") (class "Default")
      (node (ref "IC1") (pin "24") (pinfunction "P0.21/RESET_24") (pintype "bidirectional"))
      (node (ref "U$4") (pin "2") (pinfunction "4_2") (pintype "input"))
    )
    (net (code "53") (name "SCK") (class "Default")
      (node (ref "IC1") (pin "38") (pinfunction "P0.26_38") (pintype "bidirectional"))
      (node (ref "IC5") (pin "6") (pinfunction "SCK_6") (pintype "bidirectional"))
      (node (ref "IC6") (pin "6") (pinfunction "SCK_6") (pintype "bidirectional"))
    )
    (net (code "54") (name "SD") (class "Default")
      (node (ref "IC1") (pin "37") (pinfunction "P0.25_37") (pintype "bidirectional"))
      (node (ref "IC5") (pin "7") (pinfunction "SD_7") (pintype "bidirectional"))
      (node (ref "IC6") (pin "7") (pinfunction "SD_7") (pintype "bidirectional"))
      (node (ref "R2") (pin "2") (pinfunction "P$2_2") (pintype "bidirectional"))
    )
    (net (code "55") (name "SWDCLK") (class "Default")
      (node (ref "IC1") (pin "25") (pinfunction "SWDCLK_25") (pintype "bidirectional"))
      (node (ref "U$4") (pin "3") (pinfunction "3_3") (pintype "input"))
    )
    (net (code "56") (name "SWDIO") (class "Default")
      (node (ref "IC1") (pin "26") (pinfunction "SWDIO_26") (pintype "bidirectional"))
      (node (ref "U$4") (pin "4") (pinfunction "2_4") (pintype "input"))
    )
    (net (code "57") (name "VIN") (class "Default")
      (node (ref "C31") (pin "2") (pinfunction "P$2_2") (pintype "bidirectional"))
      (node (ref "IC3") (pin "1") (pinfunction "VIN_1") (pintype "bidirectional"))
      (node (ref "IC3") (pin "2") (pinfunction "VIN_2") (pintype "bidirectional"))
      (node (ref "IC3") (pin "3") (pinfunction "SHDN__3") (pintype "bidirectional"))
      (node (ref "U$2") (pin "1") (pinfunction "VIN_1") (pintype "bidirectional"))
      (node (ref "U$2") (pin "EP") (pinfunction "EP_EP") (pintype "bidirectional"))
      (node (ref "U$4") (pin "5") (pinfunction "1_5") (pintype "input"))
      (node (ref "U$5") (pin "1") (pinfunction "VIN_1") (pintype "bidirectional"))
      (node (ref "U$5") (pin "EP") (pinfunction "EP_EP") (pintype "bidirectional"))
      (node (ref "U$6") (pin "1") (pinfunction "VIN_1") (pintype "bidirectional"))
      (node (ref "U$6") (pin "EP") (pinfunction "EP_EP") (pintype "bidirectional"))
      (node (ref "X1") (pin "4") (pinfunction "S_4") (pintype "passive"))
    )
    (net (code "58") (name "WS") (class "Default")
      (node (ref "IC1") (pin "39") (pinfunction "P0.27_39") (pintype "bidirectional"))
      (node (ref "IC5") (pin "5") (pinfunction "WS_5") (pintype "bidirectional"))
      (node (ref "IC6") (pin "5") (pinfunction "WS_5") (pintype "bidirectional"))
    )
    (net (code "59") (name "unconnected-(IC1-NC-Pad44)") (class "Default")
      (node (ref "IC1") (pin "44") (pinfunction "NC_44") (pintype "bidirectional"))
    )
    (net (code "60") (name "unconnected-(IC2-NC-Pad2)") (class "Default")
      (node (ref "IC2") (pin "2") (pinfunction "NC_2") (pintype "bidirectional"))
    )
    (net (code "61") (name "unconnected-(IC2-NC-Pad3)") (class "Default")
      (node (ref "IC2") (pin "3") (pinfunction "NC_3") (pintype "bidirectional"))
    )
    (net (code "62") (name "unconnected-(IC2-NC-Pad4)") (class "Default")
      (node (ref "IC2") (pin "4") (pinfunction "NC_4") (pintype "bidirectional"))
    )
    (net (code "63") (name "unconnected-(IC2-NC-Pad5)") (class "Default")
      (node (ref "IC2") (pin "5") (pinfunction "NC_5") (pintype "bidirectional"))
    )
    (net (code "64") (name "unconnected-(IC2-NC-Pad6)") (class "Default")
      (node (ref "IC2") (pin "6") (pinfunction "NC_6") (pintype "bidirectional"))
    )
    (net (code "65") (name "unconnected-(IC2-NC-Pad14)") (class "Default")
      (node (ref "IC2") (pin "14") (pinfunction "NC_14") (pintype "bidirectional"))
    )
    (net (code "66") (name "unconnected-(IC2-NC-Pad15)") (class "Default")
      (node (ref "IC2") (pin "15") (pinfunction "NC_15") (pintype "bidirectional"))
    )
    (net (code "67") (name "unconnected-(IC2-NC-Pad16)") (class "Default")
      (node (ref "IC2") (pin "16") (pinfunction "NC_16") (pintype "bidirectional"))
    )
    (net (code "68") (name "unconnected-(IC2-NC-Pad17)") (class "Default")
      (node (ref "IC2") (pin "17") (pinfunction "NC_17") (pintype "bidirectional"))
    )
    (net (code "69") (name "unconnected-(IC2-RESV-Pad19)") (class "Default")
      (node (ref "IC2") (pin "19") (pinfunction "RESV_19") (pintype "bidirectional"))
    )
    (net (code "70") (name "unconnected-(U$4A-S1-PadM1)") (class "Default")
      (node (ref "U$4") (pin "M1") (pinfunction "S1_M1") (pintype "passive"))
    )
    (net (code "71") (name "unconnected-(U$4A-S2-PadM2)") (class "Default")
      (node (ref "U$4") (pin "M2") (pinfunction "S2_M2") (pintype "passive"))
    )
    (net (code "72") (name "unconnected-(U$4A-S3-PadM3)") (class "Default")
      (node (ref "U$4") (pin "M3") (pinfunction "S3_M3") (pintype "passive"))
    )
    (net (code "73") (name "unconnected-(U$4A-S4-PadM4)") (class "Default")
      (node (ref "U$4") (pin "M4") (pinfunction "S4_M4") (pintype "passive"))
    )
  )
)
